# basebotPower.net
KiCad netlist of a schematic drawn in EAGLE
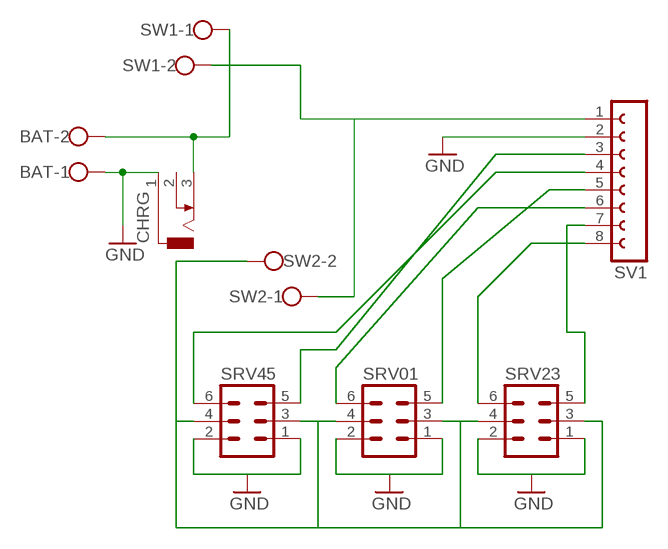
[diagram p0: schematic, sheet 1]

(export (version "E")
  (design (tool "Eeschema 10.0.6"))
  (components
    (comp (ref "BAT")
      (value "W237-102")
      (footprint "eagle-import:W237-102")
      (fields (field (name "MPN") "237-102"))
      (libsource (lib "eagle-import") (part "W237-102"))
    )
    (comp (ref "CHRG")
      (value "DCJ0303")
      (footprint "eagle-import:DCJ0303")
      (libsource (lib "eagle-import") (part "DCJ0303"))
    )
    (comp (ref "SRV01")
      (value "MA03-2")
      (footprint "eagle-import:MA03-2")
      (libsource (lib "eagle-import") (part "MA03-2"))
    )
    (comp (ref "SRV23")
      (value "MA03-2")
      (footprint "eagle-import:MA03-2")
      (libsource (lib "eagle-import") (part "MA03-2"))
    )
    (comp (ref "SRV45")
      (value "MA03-2")
      (footprint "eagle-import:MA03-2")
      (libsource (lib "eagle-import") (part "MA03-2"))
    )
    (comp (ref "SV1")
      (value "FE08-1")
      (footprint "eagle-import:FE08")
      (libsource (lib "eagle-import") (part "FE08-1"))
    )
    (comp (ref "SW1")
      (value "W237-102")
      (footprint "eagle-import:W237-102")
      (fields (field (name "MPN") "237-102"))
      (libsource (lib "eagle-import") (part "W237-102"))
    )
    (comp (ref "SW2")
      (value "W237-102")
      (footprint "eagle-import:W237-102")
      (fields (field (name "MPN") "237-102"))
      (libsource (lib "eagle-import") (part "W237-102"))
    )
  )
  (nets
    (net (code "1") (name "GND") (class "Default")
      (node (ref "BAT") (pin "1") (pinfunction "KL_1") (pintype "passive"))
      (node (ref "CHRG") (pin "1") (pinfunction "1_1") (pintype "passive"))
      (node (ref "SRV01") (pin "1") (pinfunction "1_1") (pintype "passive"))
      (node (ref "SRV01") (pin "2") (pinfunction "2_2") (pintype "passive"))
      (node (ref "SRV23") (pin "1") (pinfunction "1_1") (pintype "passive"))
      (node (ref "SRV23") (pin "2") (pinfunction "2_2") (pintype "passive"))
      (node (ref "SRV45") (pin "1") (pinfunction "1_1") (pintype "passive"))
      (node (ref "SRV45") (pin "2") (pinfunction "2_2") (pintype "passive"))
      (node (ref "SV1") (pin "2") (pinfunction "2_2") (pintype "passive"))
    )
    (net (code "2") (name "Net-(BATB-KL)") (class "Default")
      (node (ref "BAT") (pin "2") (pinfunction "KL_2") (pintype "passive"))
      (node (ref "CHRG") (pin "3") (pinfunction "3_3") (pintype "passive"))
      (node (ref "SW1") (pin "1") (pinfunction "KL_1") (pintype "passive"))
    )
    (net (code "3") (name "Net-(SRV01-Pad5)") (class "Default")
      (node (ref "SRV01") (pin "5") (pinfunction "5_5") (pintype "passive"))
      (node (ref "SV1") (pin "5") (pinfunction "5_5") (pintype "passive"))
    )
    (net (code "4") (name "Net-(SRV01-Pad6)") (class "Default")
      (node (ref "SRV01") (pin "6") (pinfunction "6_6") (pintype "passive"))
      (node (ref "SV1") (pin "6") (pinfunction "6_6") (pintype "passive"))
    )
    (net (code "5") (name "Net-(SRV23-Pad5)") (class "Default")
      (node (ref "SRV23") (pin "5") (pinfunction "5_5") (pintype "passive"))
      (node (ref "SV1") (pin "7") (pinfunction "7_7") (pintype "passive"))
    )
    (net (code "6") (name "Net-(SRV23-Pad6)") (class "Default")
      (node (ref "SRV23") (pin "6") (pinfunction "6_6") (pintype "passive"))
      (node (ref "SV1") (pin "8") (pinfunction "8_8") (pintype "passive"))
    )
    (net (code "7") (name "Net-(SRV45-Pad5)") (class "Default")
      (node (ref "SRV45") (pin "5") (pinfunction "5_5") (pintype "passive"))
      (node (ref "SV1") (pin "3") (pinfunction "3_3") (pintype "passive"))
    )
    (net (code "8") (name "Net-(SRV45-Pad6)") (class "Default")
      (node (ref "SRV45") (pin "6") (pinfunction "6_6") (pintype "passive"))
      (node (ref "SV1") (pin "4") (pinfunction "4_4") (pintype "passive"))
    )
    (net (code "9") (name "Net-(SW1B-KL)") (class "Default")
      (node (ref "SV1") (pin "1") (pinfunction "1_1") (pintype "passive"))
      (node (ref "SW1") (pin "2") (pinfunction "KL_2") (pintype "passive"))
      (node (ref "SW2") (pin "1") (pinfunction "KL_1") (pintype "passive"))
    )
    (net (code "10") (name "Net-(SW2B-KL)") (class "Default")
      (node (ref "SRV01") (pin "3") (pinfunction "3_3") (pintype "passive"))
      (node (ref "SRV01") (pin "4") (pinfunction "4_4") (pintype "passive"))
      (node (ref "SRV23") (pin "3") (pinfunction "3_3") (pintype "passive"))
      (node (ref "SRV23") (pin "4") (pinfunction "4_4") (pintype "passive"))
      (node (ref "SRV45") (pin "3") (pinfunction "3_3") (pintype "passive"))
      (node (ref "SRV45") (pin "4") (pinfunction "4_4") (pintype "passive"))
      (node (ref "SW2") (pin "2") (pinfunction "KL_2") (pintype "passive"))
    )
    (net (code "11") (name "unconnected-(CHRG-Pad2)") (class "Default")
      (node (ref "CHRG") (pin "2") (pinfunction "2_2") (pintype "passive"))
    )
  )
)
